# Grove_I2C_FM_Receiver_v1_1.net
KiCad netlist of a schematic drawn in EAGLE
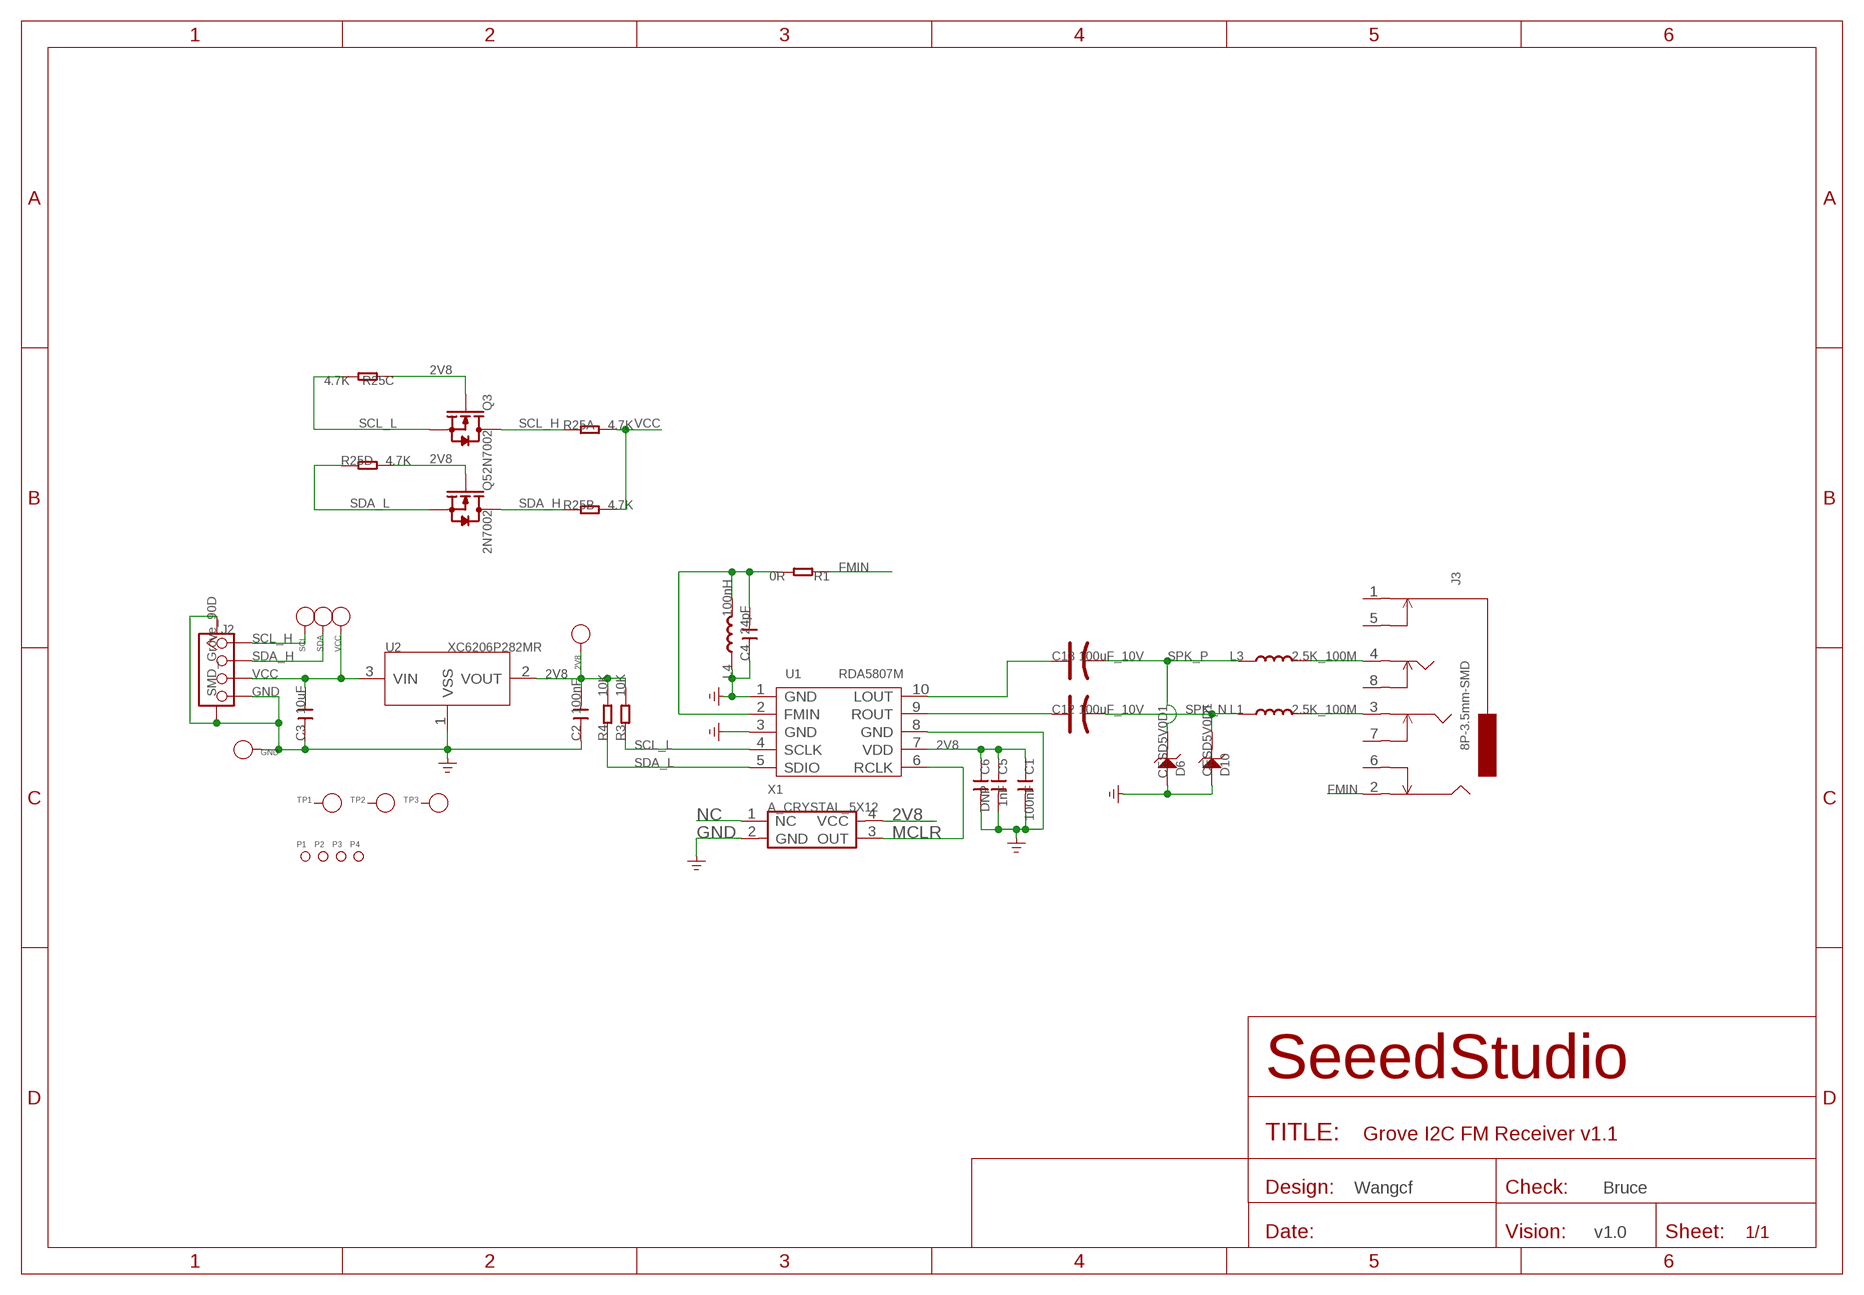
[diagram p0: schematic, sheet 1]

(export (version "E")
  (design (tool "Eeschema 10.0.6"))
  (components
    (comp (ref "2V8")
      (value "PAD-TEST-POINT'4545'")
      (footprint "eagle-import:TP_4545")
      (fields (field (name "PARTNO") "DNP"))
      (libsource (lib "eagle-import") (part "PAD-TEST-POINT'4545'"))
    )
    (comp (ref "C1")
      (value "100nF")
      (footprint "eagle-import:C0603")
      (libsource (lib "eagle-import") (part "C-0603"))
    )
    (comp (ref "C2")
      (value "100nF")
      (footprint "eagle-import:C0603")
      (libsource (lib "eagle-import") (part "C-0603"))
    )
    (comp (ref "C3")
      (value "10uF")
      (footprint "eagle-import:C0805")
      (libsource (lib "eagle-import") (part "C-0805"))
    )
    (comp (ref "C4")
      (value "24pF")
      (footprint "eagle-import:C0603")
      (libsource (lib "eagle-import") (part "C-0603"))
    )
    (comp (ref "C5")
      (value "1nF")
      (footprint "eagle-import:C0603")
      (libsource (lib "eagle-import") (part "C-0603"))
    )
    (comp (ref "C6")
      (value "DNP")
      (footprint "eagle-import:C0603")
      (libsource (lib "eagle-import") (part "C-0603"))
    )
    (comp (ref "C12")
      (value "100uF_10V")
      (footprint "eagle-import:AVX-B")
      (libsource (lib "eagle-import") (part "CAP-AVX-B"))
    )
    (comp (ref "C13")
      (value "100uF_10V")
      (footprint "eagle-import:AVX-B")
      (libsource (lib "eagle-import") (part "CAP-AVX-B"))
    )
    (comp (ref "D6")
      (value "CESD5V0D1")
      (footprint "eagle-import:SOD123-2.7X1.6")
      (libsource (lib "eagle-import") (part "D-ESD"))
    )
    (comp (ref "D10")
      (value "CESD5V0D1")
      (footprint "eagle-import:SOD123-2.7X1.6")
      (libsource (lib "eagle-import") (part "D-ESD"))
    )
    (comp (ref "GND")
      (value "PAD-TEST-POINT'4545'")
      (footprint "eagle-import:TP_4545")
      (fields (field (name "PARTNO") "DNP"))
      (libsource (lib "eagle-import") (part "PAD-TEST-POINT'4545'"))
    )
    (comp (ref "J2")
      (value "SMD_Grove_90D")
      (footprint "eagle-import:4P-SMD-2.0")
      (libsource (lib "eagle-import") (part "TWIG-4P-2.0-SMD-FEMALE-REINFORCE'DD'"))
    )
    (comp (ref "J3")
      (value "8P-3.5mm-SMD")
      (footprint "eagle-import:8P-3.5-SMD")
      (libsource (lib "eagle-import") (part "AUDIO-8P'PJ-3536-L6S'"))
    )
    (comp (ref "L1")
      (value "2.5K_100M")
      (footprint "eagle-import:L0603")
      (libsource (lib "eagle-import") (part "L'0603'"))
    )
    (comp (ref "L3")
      (value "2.5K_100M")
      (footprint "eagle-import:L0603")
      (libsource (lib "eagle-import") (part "L'0603'"))
    )
    (comp (ref "L4")
      (value "100nH")
      (footprint "eagle-import:L0603")
      (libsource (lib "eagle-import") (part "L'0603'"))
    )
    (comp (ref "P1")
      (value "PAD-MARK'ANNULAR'")
      (footprint "eagle-import:ROUND-MARK-1.0")
      (fields (field (name "PARTNO") "DNP"))
      (libsource (lib "eagle-import") (part "PAD-MARK'ANNULAR'"))
    )
    (comp (ref "P2")
      (value "PAD-MARK'ANNULAR'")
      (footprint "eagle-import:ROUND-MARK-1.0")
      (fields (field (name "PARTNO") "DNP"))
      (libsource (lib "eagle-import") (part "PAD-MARK'ANNULAR'"))
    )
    (comp (ref "P3")
      (value "PAD-MARK'ANNULAR'")
      (footprint "eagle-import:ROUND-MARK-1.0")
      (fields (field (name "PARTNO") "DNP"))
      (libsource (lib "eagle-import") (part "PAD-MARK'ANNULAR'"))
    )
    (comp (ref "P4")
      (value "PAD-MARK'ANNULAR'")
      (footprint "eagle-import:ROUND-MARK-1.0")
      (fields (field (name "PARTNO") "DNP"))
      (libsource (lib "eagle-import") (part "PAD-MARK'ANNULAR'"))
    )
    (comp (ref "Q3")
      (value "2N7002")
      (footprint "eagle-import:SOT23")
      (libsource (lib "eagle-import") (part "MOSFET-N'SOT23'"))
    )
    (comp (ref "Q5")
      (value "2N7002")
      (footprint "eagle-import:SOT23")
      (libsource (lib "eagle-import") (part "MOSFET-N'SOT23'"))
    )
    (comp (ref "R1")
      (value "0R")
      (footprint "eagle-import:R0603")
      (libsource (lib "eagle-import") (part "R-0603"))
    )
    (comp (ref "R3")
      (value "10K")
      (footprint "eagle-import:R0603")
      (libsource (lib "eagle-import") (part "R-0603"))
    )
    (comp (ref "R4")
      (value "10K")
      (footprint "eagle-import:R0603")
      (libsource (lib "eagle-import") (part "R-0603"))
    )
    (comp (ref "R25")
      (value "4.7K")
      (footprint "eagle-import:1206-8-3.3X2.4")
      (libsource (lib "eagle-import") (part "R-4R-1206"))
    )
    (comp (ref "SCL")
      (value "PAD-TEST-POINT'4545'")
      (footprint "eagle-import:TP_4545")
      (fields (field (name "PARTNO") "DNP"))
      (libsource (lib "eagle-import") (part "PAD-TEST-POINT'4545'"))
    )
    (comp (ref "SDA")
      (value "PAD-TEST-POINT'4545'")
      (footprint "eagle-import:TP_4545")
      (fields (field (name "PARTNO") "DNP"))
      (libsource (lib "eagle-import") (part "PAD-TEST-POINT'4545'"))
    )
    (comp (ref "TP1")
      (value "PAD-TEST-POINT'4545'")
      (footprint "eagle-import:TP_4545")
      (fields (field (name "PARTNO") "DNP"))
      (libsource (lib "eagle-import") (part "PAD-TEST-POINT'4545'"))
    )
    (comp (ref "TP2")
      (value "PAD-TEST-POINT'4545'")
      (footprint "eagle-import:TP_4545")
      (fields (field (name "PARTNO") "DNP"))
      (libsource (lib "eagle-import") (part "PAD-TEST-POINT'4545'"))
    )
    (comp (ref "TP3")
      (value "PAD-TEST-POINT'4545'")
      (footprint "eagle-import:TP_4545")
      (fields (field (name "PARTNO") "DNP"))
      (libsource (lib "eagle-import") (part "PAD-TEST-POINT'4545'"))
    )
    (comp (ref "U1")
      (value "RDA5807M")
      (footprint "eagle-import:MSOP10")
      (libsource (lib "eagle-import") (part "RDA5807M"))
    )
    (comp (ref "U2")
      (value "XC6206P282MR")
      (footprint "eagle-import:SOT23")
      (libsource (lib "eagle-import") (part "XC6206MR"))
    )
    (comp (ref "VCC")
      (value "PAD-TEST-POINT'4545'")
      (footprint "eagle-import:TP_4545")
      (fields (field (name "PARTNO") "DNP"))
      (libsource (lib "eagle-import") (part "PAD-TEST-POINT'4545'"))
    )
    (comp (ref "X1")
      (value "A_CRYSTAL_5X12")
      (footprint "eagle-import:4P_5X12")
      (libsource (lib "eagle-import") (part "A_CRYSTAL_5X12"))
    )
  )
  (nets
    (net (code "1") (name "/2V8") (class "Default")
      (node (ref "2V8") (pin "T") (pinfunction "T_T") (pintype "bidirectional"))
      (node (ref "C1") (pin "1") (pinfunction "1_1") (pintype "passive"))
      (node (ref "C2") (pin "2") (pinfunction "2_2") (pintype "passive"))
      (node (ref "C5") (pin "1") (pinfunction "1_1") (pintype "passive"))
      (node (ref "C6") (pin "1") (pinfunction "1_1") (pintype "passive"))
      (node (ref "Q3") (pin "1") (pinfunction "G_1") (pintype "passive"))
      (node (ref "Q5") (pin "1") (pinfunction "G_1") (pintype "passive"))
      (node (ref "R25") (pin "3") (pinfunction "1_3") (pintype "passive"))
      (node (ref "R25") (pin "5") (pinfunction "2_5") (pintype "passive"))
      (node (ref "R3") (pin "2") (pinfunction "2_2") (pintype "passive"))
      (node (ref "R4") (pin "2") (pinfunction "2_2") (pintype "passive"))
      (node (ref "U1") (pin "7") (pinfunction "VDD_7") (pintype "bidirectional"))
      (node (ref "U2") (pin "2") (pinfunction "VOUT_2") (pintype "output"))
      (node (ref "X1") (pin "4") (pinfunction "VCC_4") (pintype "bidirectional"))
    )
    (net (code "2") (name "/FMIN") (class "Default")
      (node (ref "J3") (pin "2") (pinfunction "2_2") (pintype "bidirectional"))
      (node (ref "R1") (pin "1") (pinfunction "1_1") (pintype "passive"))
    )
    (net (code "3") (name "/MCLR") (class "Default")
      (node (ref "U1") (pin "6") (pinfunction "RCLK_6") (pintype "bidirectional"))
      (node (ref "X1") (pin "3") (pinfunction "OUT_3") (pintype "bidirectional"))
    )
    (net (code "4") (name "/NC") (class "Default")
      (node (ref "X1") (pin "1") (pinfunction "NC_1") (pintype "bidirectional"))
    )
    (net (code "5") (name "/SCL_H") (class "Default")
      (node (ref "J2") (pin "1") (pinfunction "1_1") (pintype "bidirectional"))
      (node (ref "Q3") (pin "3") (pinfunction "D_3") (pintype "passive"))
      (node (ref "R25") (pin "1") (pinfunction "1_1") (pintype "passive"))
      (node (ref "SCL") (pin "T") (pinfunction "T_T") (pintype "bidirectional"))
    )
    (net (code "6") (name "/SCL_L") (class "Default")
      (node (ref "Q3") (pin "2") (pinfunction "S_2") (pintype "passive"))
      (node (ref "R25") (pin "6") (pinfunction "2_6") (pintype "passive"))
      (node (ref "R3") (pin "1") (pinfunction "1_1") (pintype "passive"))
      (node (ref "U1") (pin "4") (pinfunction "SCLK_4") (pintype "bidirectional"))
    )
    (net (code "7") (name "/SDA_H") (class "Default")
      (node (ref "J2") (pin "2") (pinfunction "2_2") (pintype "bidirectional"))
      (node (ref "Q5") (pin "3") (pinfunction "D_3") (pintype "passive"))
      (node (ref "R25") (pin "2") (pinfunction "1_2") (pintype "passive"))
      (node (ref "SDA") (pin "T") (pinfunction "T_T") (pintype "bidirectional"))
    )
    (net (code "8") (name "/SDA_L") (class "Default")
      (node (ref "Q5") (pin "2") (pinfunction "S_2") (pintype "passive"))
      (node (ref "R25") (pin "4") (pinfunction "1_4") (pintype "passive"))
      (node (ref "R4") (pin "1") (pinfunction "1_1") (pintype "passive"))
      (node (ref "U1") (pin "5") (pinfunction "SDIO_5") (pintype "bidirectional"))
    )
    (net (code "9") (name "/SPK_N") (class "Default")
      (node (ref "C12") (pin "-") (pinfunction "-_-") (pintype "passive"))
      (node (ref "D10") (pin "2") (pinfunction "2_2") (pintype "bidirectional"))
      (node (ref "L1") (pin "1") (pinfunction "1_1") (pintype "passive"))
    )
    (net (code "10") (name "/SPK_P") (class "Default")
      (node (ref "C13") (pin "-") (pinfunction "-_-") (pintype "passive"))
      (node (ref "D6") (pin "2") (pinfunction "2_2") (pintype "bidirectional"))
      (node (ref "L3") (pin "1") (pinfunction "1_1") (pintype "passive"))
    )
    (net (code "11") (name "/VCC") (class "Default")
      (node (ref "C3") (pin "2") (pinfunction "2_2") (pintype "passive"))
      (node (ref "J2") (pin "3") (pinfunction "3_3") (pintype "bidirectional"))
      (node (ref "R25") (pin "7") (pinfunction "2_7") (pintype "passive"))
      (node (ref "R25") (pin "8") (pinfunction "2_8") (pintype "passive"))
      (node (ref "U2") (pin "3") (pinfunction "VIN_3") (pintype "input"))
      (node (ref "VCC") (pin "T") (pinfunction "T_T") (pintype "bidirectional"))
    )
    (net (code "12") (name "GND_POWER") (class "Default")
      (node (ref "C1") (pin "2") (pinfunction "2_2") (pintype "passive"))
      (node (ref "C2") (pin "1") (pinfunction "1_1") (pintype "passive"))
      (node (ref "C3") (pin "1") (pinfunction "1_1") (pintype "passive"))
      (node (ref "C4") (pin "1") (pinfunction "1_1") (pintype "passive"))
      (node (ref "C5") (pin "2") (pinfunction "2_2") (pintype "passive"))
      (node (ref "C6") (pin "2") (pinfunction "2_2") (pintype "passive"))
      (node (ref "D10") (pin "1") (pinfunction "1_1") (pintype "bidirectional"))
      (node (ref "D6") (pin "1") (pinfunction "1_1") (pintype "bidirectional"))
      (node (ref "GND") (pin "T") (pinfunction "T_T") (pintype "bidirectional"))
      (node (ref "J2") (pin "4") (pinfunction "4_4") (pintype "bidirectional"))
      (node (ref "J2") (pin "SS1") (pinfunction "SS1_SS1") (pintype "bidirectional"))
      (node (ref "J2") (pin "SS2") (pinfunction "SS2_SS2") (pintype "bidirectional"))
      (node (ref "L4") (pin "1") (pinfunction "1_1") (pintype "passive"))
      (node (ref "U1") (pin "1") (pinfunction "GND_1") (pintype "bidirectional"))
      (node (ref "U1") (pin "3") (pinfunction "GND_3") (pintype "bidirectional"))
      (node (ref "U1") (pin "8") (pinfunction "GND_8") (pintype "bidirectional"))
      (node (ref "U2") (pin "1") (pinfunction "VSS_1") (pintype "power_in"))
      (node (ref "X1") (pin "2") (pinfunction "GND_2") (pintype "bidirectional"))
    )
    (net (code "13") (name "Net-(J3-Pad3)") (class "Default")
      (node (ref "J3") (pin "3") (pinfunction "3_3") (pintype "bidirectional"))
      (node (ref "L1") (pin "2") (pinfunction "2_2") (pintype "passive"))
    )
    (net (code "14") (name "Net-(J3-Pad4)") (class "Default")
      (node (ref "J3") (pin "4") (pinfunction "4_4") (pintype "bidirectional"))
      (node (ref "L3") (pin "2") (pinfunction "2_2") (pintype "passive"))
    )
    (net (code "15") (name "Net-(U1-FMIN)") (class "Default")
      (node (ref "C4") (pin "2") (pinfunction "2_2") (pintype "passive"))
      (node (ref "L4") (pin "2") (pinfunction "2_2") (pintype "passive"))
      (node (ref "R1") (pin "2") (pinfunction "2_2") (pintype "passive"))
      (node (ref "U1") (pin "2") (pinfunction "FMIN_2") (pintype "bidirectional"))
    )
    (net (code "16") (name "Net-(U1-LOUT)") (class "Default")
      (node (ref "C13") (pin "+") (pinfunction "+_+") (pintype "passive"))
      (node (ref "U1") (pin "10") (pinfunction "LOUT_10") (pintype "bidirectional"))
    )
    (net (code "17") (name "Net-(U1-ROUT)") (class "Default")
      (node (ref "C12") (pin "+") (pinfunction "+_+") (pintype "passive"))
      (node (ref "U1") (pin "9") (pinfunction "ROUT_9") (pintype "bidirectional"))
    )
    (net (code "18") (name "unconnected-(J3-Pad1)") (class "Default")
      (node (ref "J3") (pin "1") (pinfunction "1_1") (pintype "bidirectional"))
    )
    (net (code "19") (name "unconnected-(J3-Pad5)") (class "Default")
      (node (ref "J3") (pin "5") (pinfunction "5_5") (pintype "bidirectional"))
    )
    (net (code "20") (name "unconnected-(J3-Pad6)") (class "Default")
      (node (ref "J3") (pin "6") (pinfunction "6_6") (pintype "bidirectional"))
    )
    (net (code "21") (name "unconnected-(J3-Pad7)") (class "Default")
      (node (ref "J3") (pin "7") (pinfunction "7_7") (pintype "bidirectional"))
    )
    (net (code "22") (name "unconnected-(J3-Pad8)") (class "Default")
      (node (ref "J3") (pin "8") (pinfunction "8_8") (pintype "bidirectional"))
    )
    (net (code "23") (name "unconnected-(TP1-PadT)") (class "Default")
      (node (ref "TP1") (pin "T") (pinfunction "T_T") (pintype "bidirectional"))
    )
    (net (code "24") (name "unconnected-(TP2-PadT)") (class "Default")
      (node (ref "TP2") (pin "T") (pinfunction "T_T") (pintype "bidirectional"))
    )
    (net (code "25") (name "unconnected-(TP3-PadT)") (class "Default")
      (node (ref "TP3") (pin "T") (pinfunction "T_T") (pintype "bidirectional"))
    )
  )
)
